# fp_bnc.net
KiCad netlist of a schematic drawn in EAGLE
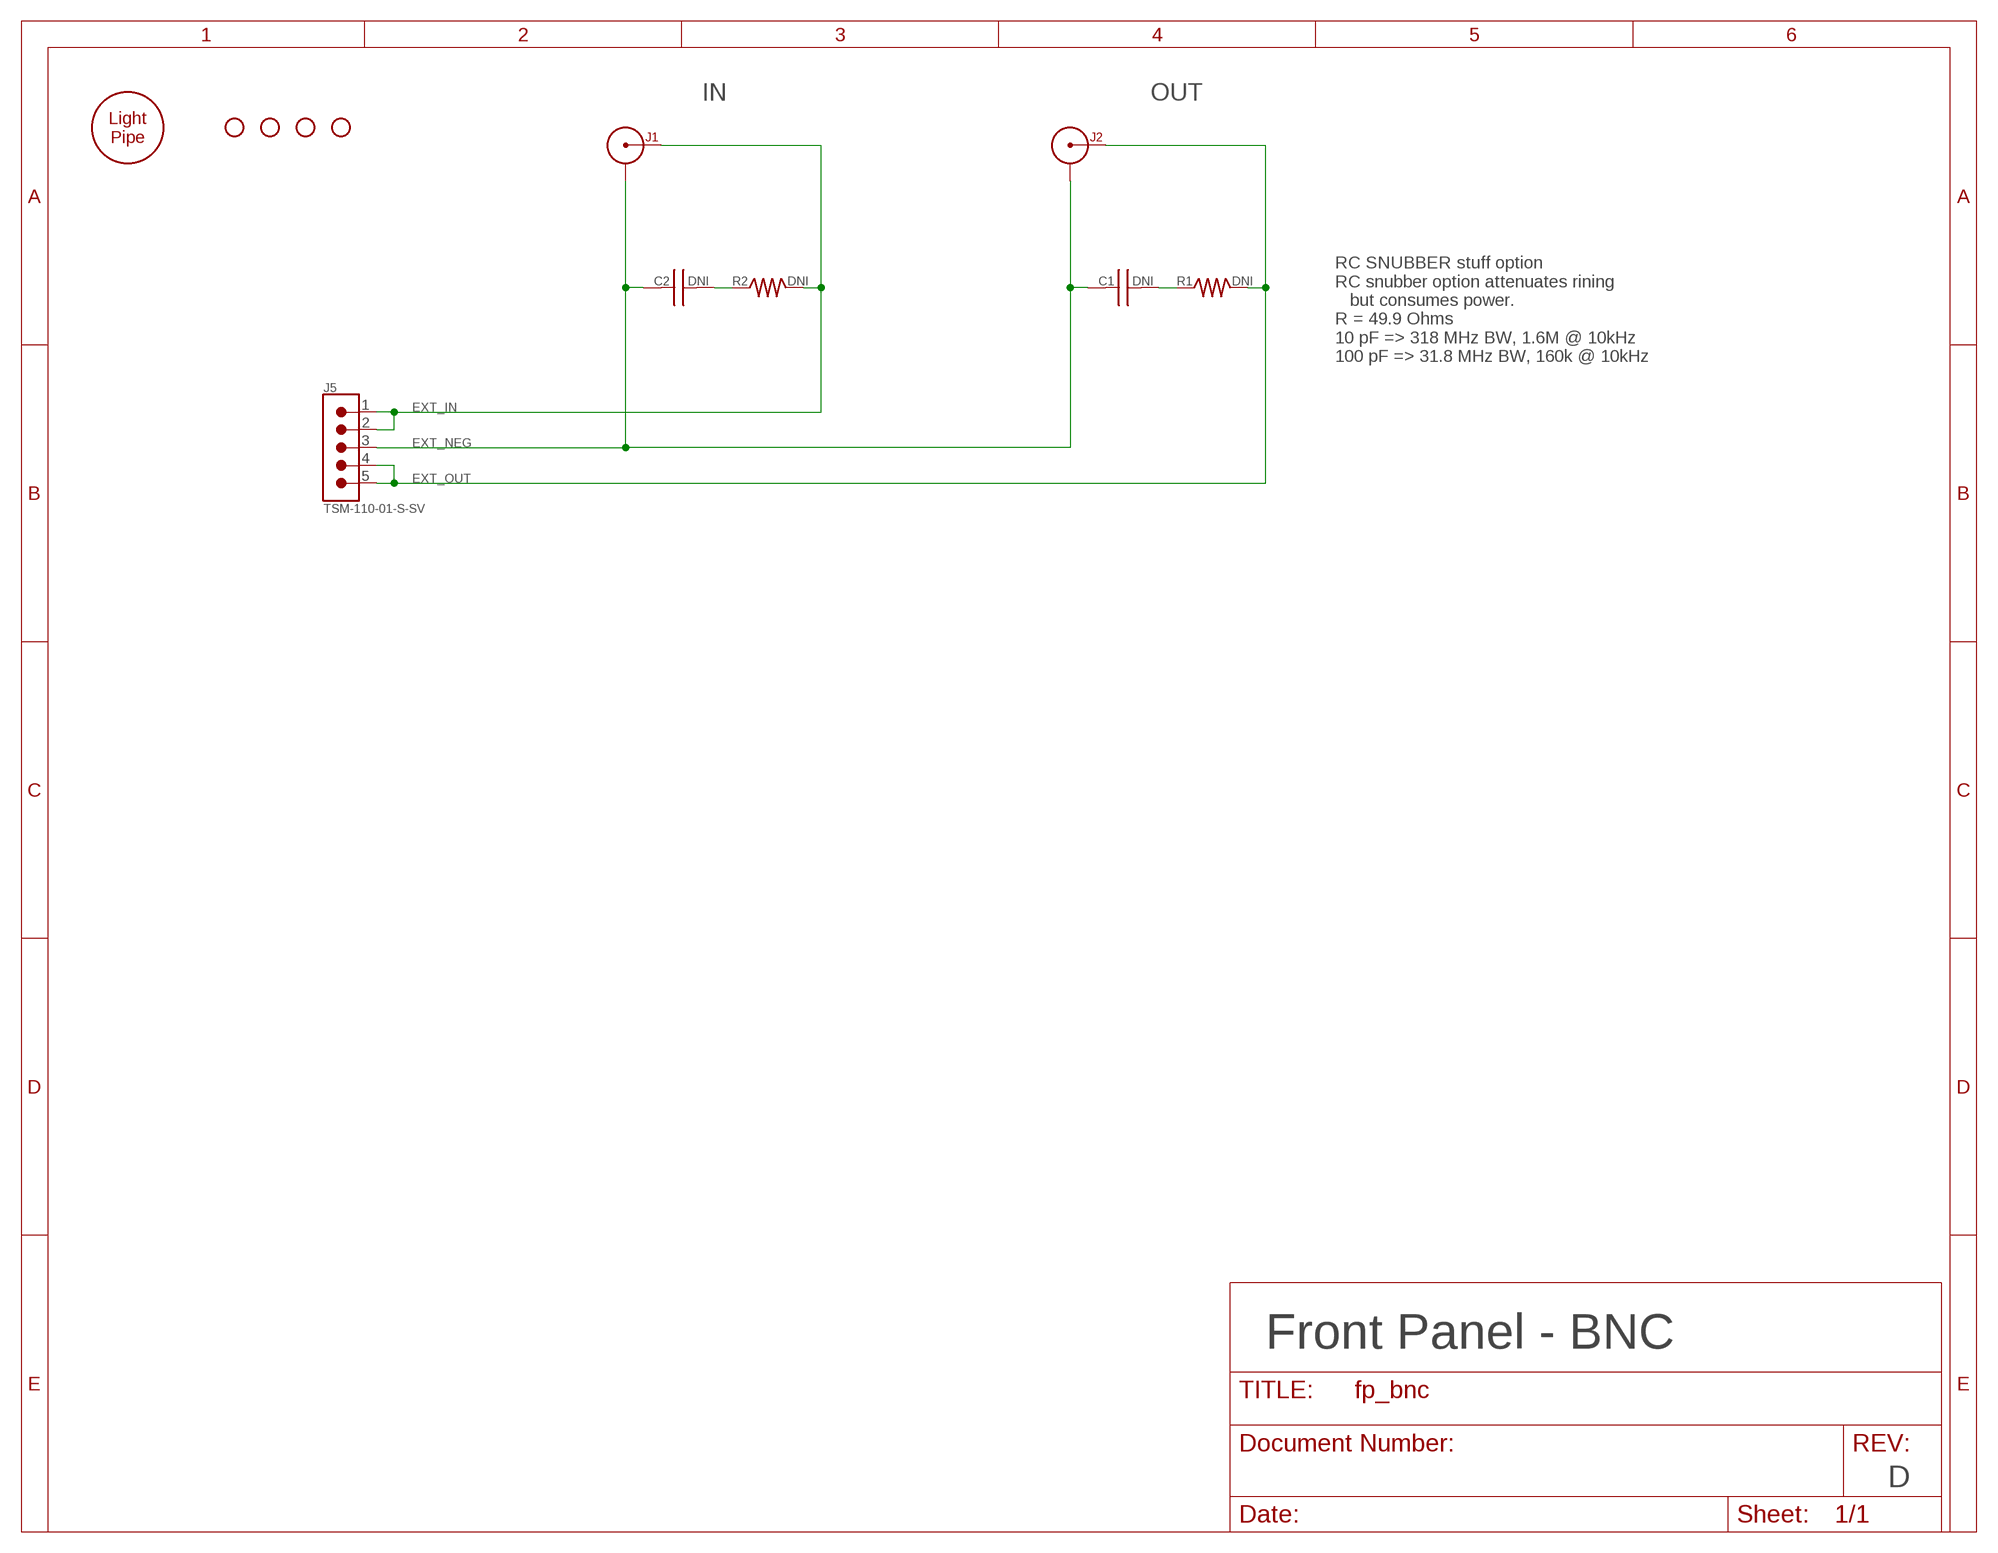
[diagram p0: schematic, sheet 1]

(export (version "E")
  (design (tool "Eeschema 10.0.6"))
  (components
    (comp (ref "C1")
      (value "DNI")
      (footprint "eagle-import:0603")
      (libsource (lib "eagle-import") (part "CAP_0603"))
    )
    (comp (ref "C2")
      (value "DNI")
      (footprint "eagle-import:0603")
      (libsource (lib "eagle-import") (part "CAP_0603"))
    )
    (comp (ref "H1")
      (value "51513020125F")
      (footprint "eagle-import:LP_3MM")
      (fields (field (name "MPN") "51513020125F"))
      (libsource (lib "eagle-import") (part "LIGHT_PIPE_PANEL_3MM"))
    )
    (comp (ref "H2")
      (value "HOLE_#6")
      (footprint "eagle-import:HOLE_3.5MM")
      (libsource (lib "eagle-import") (part "HOLE_#6"))
    )
    (comp (ref "H3")
      (value "HOLE_#6")
      (footprint "eagle-import:HOLE_3.5MM")
      (libsource (lib "eagle-import") (part "HOLE_#6"))
    )
    (comp (ref "H4")
      (value "HOLE_#6")
      (footprint "eagle-import:HOLE_3.5MM")
      (libsource (lib "eagle-import") (part "HOLE_#6"))
    )
    (comp (ref "H5")
      (value "HOLE_#6")
      (footprint "eagle-import:HOLE_3.5MM")
      (libsource (lib "eagle-import") (part "HOLE_#6"))
    )
    (comp (ref "J1")
      (value "031-5329-52RFX")
      (footprint "eagle-import:BNC_31-5329-52RFX")
      (libsource (lib "eagle-import") (part "BNC_JACKBNC_31-5329-52RFX"))
    )
    (comp (ref "J2")
      (value "031-5329-52RFX")
      (footprint "eagle-import:BNC_31-5329-52RFX")
      (libsource (lib "eagle-import") (part "BNC_JACKBNC_31-5329-52RFX"))
    )
    (comp (ref "J5")
      (value "TSM-110-01-S-SV")
      (footprint "eagle-import:CONN_0.1_5X1_MS")
      (libsource (lib "eagle-import") (part "CONN_0.1_5X1_MS"))
    )
    (comp (ref "R1")
      (value "DNI")
      (footprint "eagle-import:1206")
      (libsource (lib "eagle-import") (part "RESISTOR_1206"))
    )
    (comp (ref "R2")
      (value "DNI")
      (footprint "eagle-import:1206")
      (libsource (lib "eagle-import") (part "RESISTOR_1206"))
    )
  )
  (nets
    (net (code "1") (name "/EXT_IN") (class "Default")
      (node (ref "J1") (pin "SIGNAL") (pinfunction "SIGNAL_SIGNAL") (pintype "bidirectional"))
      (node (ref "J5") (pin "1") (pinfunction "1_1") (pintype "bidirectional"))
      (node (ref "J5") (pin "2") (pinfunction "2_2") (pintype "bidirectional"))
      (node (ref "R2") (pin "2") (pinfunction "P$2_2") (pintype "bidirectional"))
    )
    (net (code "2") (name "/EXT_NEG") (class "Default")
      (node (ref "C1") (pin "1") (pinfunction "1_1") (pintype "bidirectional"))
      (node (ref "C2") (pin "1") (pinfunction "1_1") (pintype "bidirectional"))
      (node (ref "J1") (pin "G@1") (pinfunction "SHIELD_G@1") (pintype "bidirectional"))
      (node (ref "J1") (pin "G@2") (pinfunction "SHIELD_G@2") (pintype "bidirectional"))
      (node (ref "J1") (pin "G@3") (pinfunction "SHIELD_G@3") (pintype "bidirectional"))
      (node (ref "J1") (pin "G@4") (pinfunction "SHIELD_G@4") (pintype "bidirectional"))
      (node (ref "J2") (pin "G@1") (pinfunction "SHIELD_G@1") (pintype "bidirectional"))
      (node (ref "J2") (pin "G@2") (pinfunction "SHIELD_G@2") (pintype "bidirectional"))
      (node (ref "J2") (pin "G@3") (pinfunction "SHIELD_G@3") (pintype "bidirectional"))
      (node (ref "J2") (pin "G@4") (pinfunction "SHIELD_G@4") (pintype "bidirectional"))
      (node (ref "J5") (pin "3") (pinfunction "3_3") (pintype "bidirectional"))
    )
    (net (code "3") (name "/EXT_OUT") (class "Default")
      (node (ref "J2") (pin "SIGNAL") (pinfunction "SIGNAL_SIGNAL") (pintype "bidirectional"))
      (node (ref "J5") (pin "4") (pinfunction "4_4") (pintype "bidirectional"))
      (node (ref "J5") (pin "5") (pinfunction "5_5") (pintype "bidirectional"))
      (node (ref "R1") (pin "2") (pinfunction "P$2_2") (pintype "bidirectional"))
    )
    (net (code "4") (name "Net-(R1-P$1)") (class "Default")
      (node (ref "C1") (pin "2") (pinfunction "2_2") (pintype "bidirectional"))
      (node (ref "R1") (pin "1") (pinfunction "P$1_1") (pintype "bidirectional"))
    )
    (net (code "5") (name "Net-(R2-P$1)") (class "Default")
      (node (ref "C2") (pin "2") (pinfunction "2_2") (pintype "bidirectional"))
      (node (ref "R2") (pin "1") (pinfunction "P$1_1") (pintype "bidirectional"))
    )
  )
)
